# DCDC_5V.net
KiCad netlist of a schematic drawn in Altium Designer
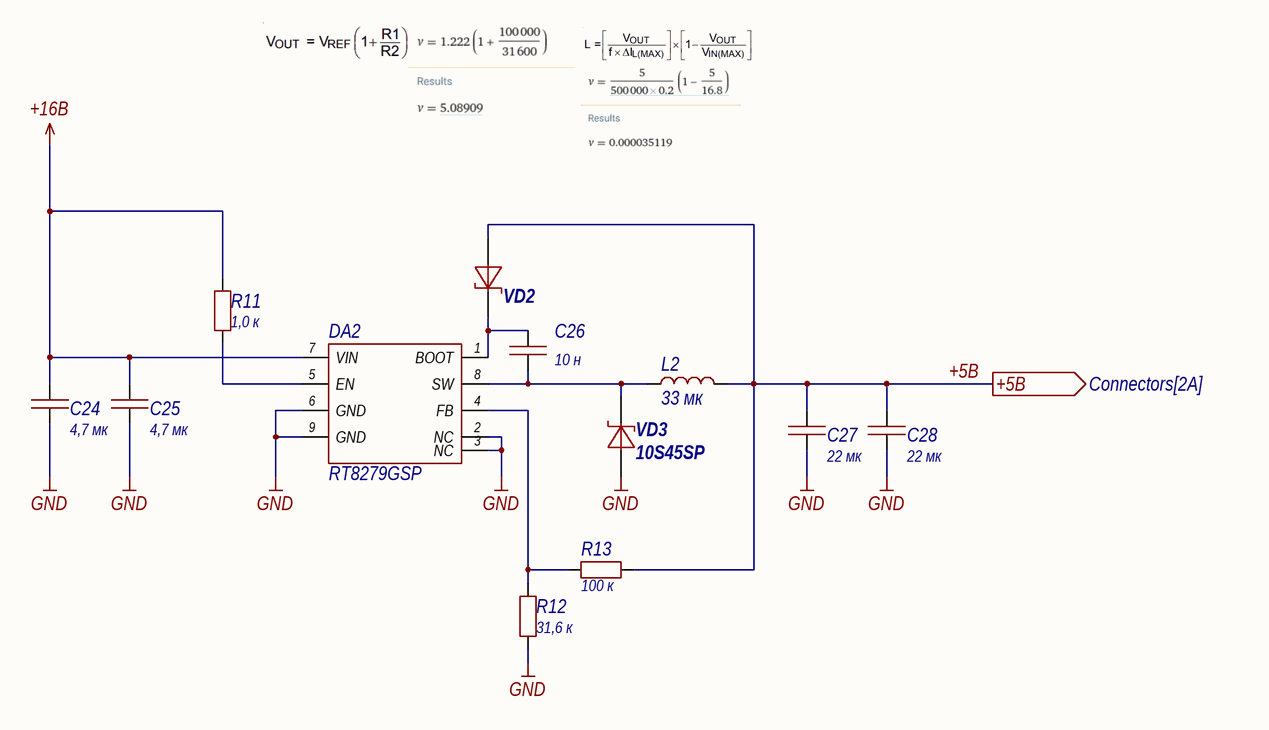
[diagram p0: DCDC_5V.SchDoc]

(export (version "E")
  (design (tool "Eeschema 10.0.6"))
  (components
    (comp (ref "C24")
      (value "4,7 мк")
      (footprint "1206C")
      (description "Конденсатор")
      (fields (field (name "PART NUMBER") "Capacitor_4,7u_10_50V_X7R_1206C") (field (name "TOLERANCE") "0,1"))
      (libsource (lib "Hydrolib") (part "Capacitor"))
    )
    (comp (ref "C25")
      (value "4,7 мк")
      (footprint "1206C")
      (description "Конденсатор")
      (fields (field (name "PART NUMBER") "Capacitor_4,7u_10_50V_X7R_1206C") (field (name "TOLERANCE") "0,1"))
      (libsource (lib "Hydrolib") (part "Capacitor"))
    )
    (comp (ref "C26")
      (value "10 н")
      (footprint "0603C")
      (description "Конденсатор")
      (fields (field (name "PART NUMBER") "Capacitor_10n_10_50V_X7R_0603C") (field (name "TOLERANCE") "0,1"))
      (libsource (lib "Hydrolib") (part "Capacitor"))
    )
    (comp (ref "C27")
      (value "22 мк")
      (footprint "1210C")
      (description "Конденсатор")
      (fields (field (name "PART NUMBER") "Capacitor_22u_10_25V_X7R_1210C") (field (name "TOLERANCE") "0,1"))
      (libsource (lib "Hydrolib") (part "Capacitor"))
    )
    (comp (ref "C28")
      (value "22 мк")
      (footprint "1210C")
      (description "Конденсатор")
      (fields (field (name "PART NUMBER") "Capacitor_22u_10_25V_X7R_1210C") (field (name "TOLERANCE") "0,1"))
      (libsource (lib "Hydrolib") (part "Capacitor"))
    )
    (comp (ref "DA2")
      (value "RT8279GSP")
      (footprint "8SOP(Exposed_Pad)")
      (description "Преобразователь постоянного тока понижающий подстраиваемый выход 5А")
      (libsource (lib "Hydrolib") (part "RT8279GSP"))
    )
    (comp (ref "L2")
      (value "33 мк")
      (footprint "IHLP-4040")
      (description "ЧИП-индуктивность экранированная 33мкГн ±20% 4,4A 94,5мОм 4040")
      (fields (field (name "PART NUMBER") "IHLP4040DZER330M11"))
      (libsource (lib "Hydrolib") (part "Inductance"))
    )
    (comp (ref "R11")
      (value "1,0 к")
      (footprint "0603R")
      (description "Резистор номиналом 1,0 кОм и точностью 1%")
      (fields (field (name "PART NUMBER") "Resistor_1.0k_1_0603") (field (name "TOLERANCE") "1%"))
      (libsource (lib "Hydrolib") (part "Resistor"))
    )
    (comp (ref "R12")
      (value "31,6 к")
      (footprint "0603R")
      (description "Резистор номиналом 31,6 кОм и точностью 1%")
      (fields (field (name "PART NUMBER") "Resistor_31.6k_1_0603") (field (name "TOLERANCE") "1%"))
      (libsource (lib "Hydrolib") (part "Resistor"))
    )
    (comp (ref "R13")
      (value "100 к")
      (footprint "0603R")
      (description "Резистор номиналом 100 кОм и точностью 1%")
      (fields (field (name "PART NUMBER") "Resistor_100k_1_0603") (field (name "TOLERANCE") "1%"))
      (libsource (lib "") (part "Resistor_1"))
    )
    (comp (ref "VD2")
      (value "BAT54WS")
      (footprint "SOD-323")
      (description "Диод шоттки на 30 В, ном. ток 0.2 А")
      (libsource (lib "Hydrolib") (part "Schottky_diode"))
    )
    (comp (ref "VD3")
      (value "10S45SP")
      (footprint "TO-277")
      (description "Диод шоттки на 45 В, ном. ток 10 А")
      (libsource (lib "Hydrolib") (part "Schottky_diode"))
    )
  )
  (nets
    (net (code "1") (name "+16В") (class "Default")
      (node (ref "C24") (pin "2") (pinfunction "2_2") (pintype "passive"))
      (node (ref "C25") (pin "2") (pinfunction "2_2") (pintype "passive"))
      (node (ref "DA2") (pin "7") (pinfunction "VIN_7") (pintype "passive"))
      (node (ref "R11") (pin "2") (pinfunction "2_2") (pintype "passive"))
    )
    (net (code "2") (name "/+5В") (class "Default")
      (node (ref "C27") (pin "2") (pinfunction "2_2") (pintype "passive"))
      (node (ref "C28") (pin "2") (pinfunction "2_2") (pintype "passive"))
      (node (ref "L2") (pin "2") (pinfunction "2_2") (pintype "passive"))
      (node (ref "R13") (pin "2") (pinfunction "2_2") (pintype "passive"))
      (node (ref "VD2") (pin "1") (pinfunction "1_1") (pintype "passive"))
    )
    (net (code "3") (name "GND") (class "Default")
      (node (ref "C24") (pin "1") (pinfunction "1_1") (pintype "passive"))
      (node (ref "C25") (pin "1") (pinfunction "1_1") (pintype "passive"))
      (node (ref "C27") (pin "1") (pinfunction "1_1") (pintype "passive"))
      (node (ref "C28") (pin "1") (pinfunction "1_1") (pintype "passive"))
      (node (ref "DA2") (pin "2") (pinfunction "NC_2") (pintype "passive"))
      (node (ref "DA2") (pin "3") (pinfunction "NC_3") (pintype "passive"))
      (node (ref "DA2") (pin "6") (pinfunction "GND_6") (pintype "passive"))
      (node (ref "DA2") (pin "9") (pinfunction "GND_9") (pintype "passive"))
      (node (ref "R12") (pin "1") (pinfunction "1_1") (pintype "passive"))
      (node (ref "VD3") (pin "1") (pinfunction "1_1") (pintype "passive"))
    )
    (net (code "4") (name "Net-(DA2-BOOT)") (class "Default")
      (node (ref "C26") (pin "2") (pinfunction "2_2") (pintype "passive"))
      (node (ref "DA2") (pin "1") (pinfunction "BOOT_1") (pintype "passive"))
      (node (ref "VD2") (pin "2") (pinfunction "2_2") (pintype "passive"))
    )
    (net (code "5") (name "Net-(DA2-EN)") (class "Default")
      (node (ref "DA2") (pin "5") (pinfunction "EN_5") (pintype "passive"))
      (node (ref "R11") (pin "1") (pinfunction "1_1") (pintype "passive"))
    )
    (net (code "6") (name "Net-(DA2-FB)") (class "Default")
      (node (ref "DA2") (pin "4") (pinfunction "FB_4") (pintype "passive"))
      (node (ref "R12") (pin "2") (pinfunction "2_2") (pintype "passive"))
      (node (ref "R13") (pin "1") (pinfunction "1_1") (pintype "passive"))
    )
    (net (code "7") (name "Net-(DA2-SW)") (class "Default")
      (node (ref "C26") (pin "1") (pinfunction "1_1") (pintype "passive"))
      (node (ref "DA2") (pin "8") (pinfunction "SW_8") (pintype "passive"))
      (node (ref "L2") (pin "1") (pinfunction "1_1") (pintype "passive"))
      (node (ref "VD3") (pin "2") (pinfunction "2_2") (pintype "passive"))
    )
  )
)
